# Display.net
KiCad netlist of a schematic drawn in EAGLE
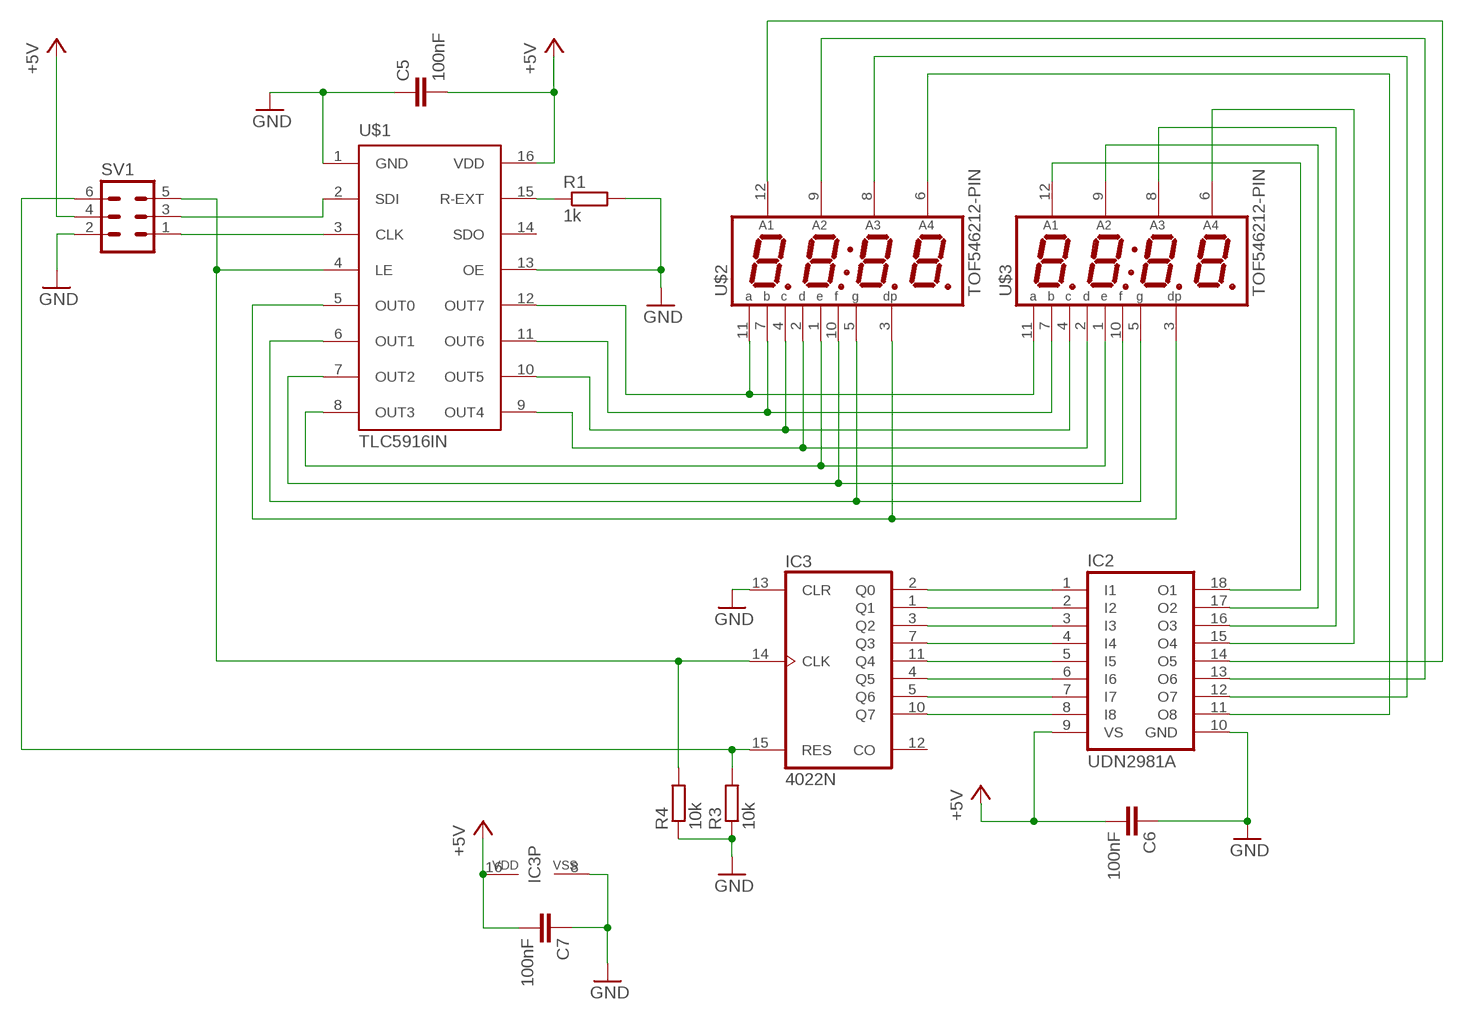
[diagram p0: schematic, sheet 1]

(export (version "E")
  (design (tool "Eeschema 10.0.6"))
  (components
    (comp (ref "C5")
      (value "100nF")
      (footprint "eagle-import:C025-024X044")
      (libsource (lib "eagle-import") (part "C-EU025-024X044"))
    )
    (comp (ref "C6")
      (value "100nF")
      (footprint "eagle-import:C025-024X044")
      (libsource (lib "eagle-import") (part "C-EU025-024X044"))
    )
    (comp (ref "C7")
      (value "100nF")
      (footprint "eagle-import:C025-024X044")
      (libsource (lib "eagle-import") (part "C-EU025-024X044"))
    )
    (comp (ref "IC2")
      (value "UDN2981A")
      (footprint "eagle-import:DIL18")
      (libsource (lib "eagle-import") (part "UDN298A1"))
    )
    (comp (ref "IC3")
      (value "4022N")
      (footprint "eagle-import:DIL16")
      (libsource (lib "eagle-import") (part "4022N"))
    )
    (comp (ref "R1")
      (value "1k")
      (footprint "eagle-import:0204_7")
      (libsource (lib "eagle-import") (part "R-EU_0204/7"))
    )
    (comp (ref "R3")
      (value "10k")
      (footprint "eagle-import:0204V")
      (libsource (lib "eagle-import") (part "R-EU_0204/2V"))
    )
    (comp (ref "R4")
      (value "10k")
      (footprint "eagle-import:0204V")
      (libsource (lib "eagle-import") (part "R-EU_0204/2V"))
    )
    (comp (ref "SV1")
      (value "ML6L")
      (footprint "eagle-import:ML6L")
      (libsource (lib "eagle-import") (part "ML6L"))
    )
    (comp (ref "U$1")
      (value "TLC5916IN")
      (footprint "eagle-import:DIL16")
      (libsource (lib "eagle-import") (part "TLC5916IN"))
    )
    (comp (ref "U$2")
      (value "TOF546212-PIN")
      (footprint "eagle-import:TOF5462_")
      (libsource (lib "eagle-import") (part "TOF546212-PIN"))
    )
    (comp (ref "U$3")
      (value "TOF546212-PIN")
      (footprint "eagle-import:TOF5462_")
      (libsource (lib "eagle-import") (part "TOF546212-PIN"))
    )
  )
  (nets
    (net (code "1") (name "+5V") (class "Default")
      (node (ref "C5") (pin "2") (pinfunction "2_2") (pintype "passive"))
      (node (ref "C6") (pin "2") (pinfunction "2_2") (pintype "passive"))
      (node (ref "C7") (pin "2") (pinfunction "2_2") (pintype "passive"))
      (node (ref "IC2") (pin "9") (pinfunction "VS_9") (pintype "passive"))
      (node (ref "IC3") (pin "16") (pinfunction "VDD_16") (pintype "power_in"))
      (node (ref "SV1") (pin "4") (pinfunction "4_4") (pintype "passive"))
      (node (ref "U$1") (pin "16") (pinfunction "VDD_16") (pintype "power_in"))
    )
    (net (code "2") (name "GND") (class "Default")
      (node (ref "C5") (pin "1") (pinfunction "1_1") (pintype "passive"))
      (node (ref "C6") (pin "1") (pinfunction "1_1") (pintype "passive"))
      (node (ref "C7") (pin "1") (pinfunction "1_1") (pintype "passive"))
      (node (ref "IC2") (pin "10") (pinfunction "GND_10") (pintype "power_in"))
      (node (ref "IC3") (pin "13") (pinfunction "CLR_13") (pintype "input"))
      (node (ref "IC3") (pin "8") (pinfunction "VSS_8") (pintype "power_in"))
      (node (ref "R1") (pin "2") (pinfunction "2_2") (pintype "passive"))
      (node (ref "R3") (pin "1") (pinfunction "1_1") (pintype "passive"))
      (node (ref "R4") (pin "1") (pinfunction "1_1") (pintype "passive"))
      (node (ref "SV1") (pin "2") (pinfunction "2_2") (pintype "passive"))
      (node (ref "U$1") (pin "1") (pinfunction "GND_1") (pintype "power_in"))
      (node (ref "U$1") (pin "13") (pinfunction "OE_13") (pintype "input"))
    )
    (net (code "3") (name "Net-(IC2-I1)") (class "Default")
      (node (ref "IC2") (pin "1") (pinfunction "I1_1") (pintype "input"))
      (node (ref "IC3") (pin "2") (pinfunction "Q0_2") (pintype "output"))
    )
    (net (code "4") (name "Net-(IC2-I2)") (class "Default")
      (node (ref "IC2") (pin "2") (pinfunction "I2_2") (pintype "input"))
      (node (ref "IC3") (pin "1") (pinfunction "Q1_1") (pintype "output"))
    )
    (net (code "5") (name "Net-(IC2-I3)") (class "Default")
      (node (ref "IC2") (pin "3") (pinfunction "I3_3") (pintype "input"))
      (node (ref "IC3") (pin "3") (pinfunction "Q2_3") (pintype "output"))
    )
    (net (code "6") (name "Net-(IC2-I4)") (class "Default")
      (node (ref "IC2") (pin "4") (pinfunction "I4_4") (pintype "input"))
      (node (ref "IC3") (pin "7") (pinfunction "Q3_7") (pintype "output"))
    )
    (net (code "7") (name "Net-(IC2-I5)") (class "Default")
      (node (ref "IC2") (pin "5") (pinfunction "I5_5") (pintype "input"))
      (node (ref "IC3") (pin "11") (pinfunction "Q4_11") (pintype "output"))
    )
    (net (code "8") (name "Net-(IC2-I6)") (class "Default")
      (node (ref "IC2") (pin "6") (pinfunction "I6_6") (pintype "input"))
      (node (ref "IC3") (pin "4") (pinfunction "Q5_4") (pintype "output"))
    )
    (net (code "9") (name "Net-(IC2-I7)") (class "Default")
      (node (ref "IC2") (pin "7") (pinfunction "I7_7") (pintype "input"))
      (node (ref "IC3") (pin "5") (pinfunction "Q6_5") (pintype "output"))
    )
    (net (code "10") (name "Net-(IC2-I8)") (class "Default")
      (node (ref "IC2") (pin "8") (pinfunction "I8_8") (pintype "input"))
      (node (ref "IC3") (pin "10") (pinfunction "Q7_10") (pintype "output"))
    )
    (net (code "11") (name "Net-(IC2-O1)") (class "Default")
      (node (ref "IC2") (pin "18") (pinfunction "O1_18") (pintype "open_collector"))
      (node (ref "U$3") (pin "12") (pinfunction "A1_12") (pintype "passive"))
    )
    (net (code "12") (name "Net-(IC2-O2)") (class "Default")
      (node (ref "IC2") (pin "17") (pinfunction "O2_17") (pintype "open_collector"))
      (node (ref "U$3") (pin "9") (pinfunction "A2_9") (pintype "passive"))
    )
    (net (code "13") (name "Net-(IC2-O3)") (class "Default")
      (node (ref "IC2") (pin "16") (pinfunction "O3_16") (pintype "open_collector"))
      (node (ref "U$3") (pin "8") (pinfunction "A3_8") (pintype "passive"))
    )
    (net (code "14") (name "Net-(IC2-O4)") (class "Default")
      (node (ref "IC2") (pin "15") (pinfunction "O4_15") (pintype "open_collector"))
      (node (ref "U$3") (pin "6") (pinfunction "A4_6") (pintype "passive"))
    )
    (net (code "15") (name "Net-(IC2-O5)") (class "Default")
      (node (ref "IC2") (pin "14") (pinfunction "O5_14") (pintype "open_collector"))
      (node (ref "U$2") (pin "12") (pinfunction "A1_12") (pintype "passive"))
    )
    (net (code "16") (name "Net-(IC2-O6)") (class "Default")
      (node (ref "IC2") (pin "13") (pinfunction "O6_13") (pintype "open_collector"))
      (node (ref "U$2") (pin "9") (pinfunction "A2_9") (pintype "passive"))
    )
    (net (code "17") (name "Net-(IC2-O7)") (class "Default")
      (node (ref "IC2") (pin "12") (pinfunction "O7_12") (pintype "open_collector"))
      (node (ref "U$2") (pin "8") (pinfunction "A3_8") (pintype "passive"))
    )
    (net (code "18") (name "Net-(IC2-O8)") (class "Default")
      (node (ref "IC2") (pin "11") (pinfunction "O8_11") (pintype "open_collector"))
      (node (ref "U$2") (pin "6") (pinfunction "A4_6") (pintype "passive"))
    )
    (net (code "19") (name "Net-(IC3A-CLK)") (class "Default")
      (node (ref "IC3") (pin "14") (pinfunction "CLK_14") (pintype "input"))
      (node (ref "R4") (pin "2") (pinfunction "2_2") (pintype "passive"))
      (node (ref "SV1") (pin "5") (pinfunction "5_5") (pintype "passive"))
      (node (ref "U$1") (pin "4") (pinfunction "LE_4") (pintype "input"))
    )
    (net (code "20") (name "Net-(IC3A-RES)") (class "Default")
      (node (ref "IC3") (pin "15") (pinfunction "RES_15") (pintype "input"))
      (node (ref "R3") (pin "2") (pinfunction "2_2") (pintype "passive"))
      (node (ref "SV1") (pin "6") (pinfunction "6_6") (pintype "passive"))
    )
    (net (code "21") (name "Net-(U$1-CLK)") (class "Default")
      (node (ref "SV1") (pin "1") (pinfunction "1_1") (pintype "passive"))
      (node (ref "U$1") (pin "3") (pinfunction "CLK_3") (pintype "input"))
    )
    (net (code "22") (name "Net-(U$1-OUT0)") (class "Default")
      (node (ref "U$1") (pin "5") (pinfunction "OUT0_5") (pintype "output"))
      (node (ref "U$2") (pin "3") (pinfunction "DP_3") (pintype "passive"))
      (node (ref "U$3") (pin "3") (pinfunction "DP_3") (pintype "passive"))
    )
    (net (code "23") (name "Net-(U$1-OUT1)") (class "Default")
      (node (ref "U$1") (pin "6") (pinfunction "OUT1_6") (pintype "output"))
      (node (ref "U$2") (pin "5") (pinfunction "G_5") (pintype "passive"))
      (node (ref "U$3") (pin "5") (pinfunction "G_5") (pintype "passive"))
    )
    (net (code "24") (name "Net-(U$1-OUT2)") (class "Default")
      (node (ref "U$1") (pin "7") (pinfunction "OUT2_7") (pintype "output"))
      (node (ref "U$2") (pin "10") (pinfunction "F_10") (pintype "passive"))
      (node (ref "U$3") (pin "10") (pinfunction "F_10") (pintype "passive"))
    )
    (net (code "25") (name "Net-(U$1-OUT3)") (class "Default")
      (node (ref "U$1") (pin "8") (pinfunction "OUT3_8") (pintype "output"))
      (node (ref "U$2") (pin "1") (pinfunction "E_1") (pintype "passive"))
      (node (ref "U$3") (pin "1") (pinfunction "E_1") (pintype "passive"))
    )
    (net (code "26") (name "Net-(U$1-OUT4)") (class "Default")
      (node (ref "U$1") (pin "9") (pinfunction "OUT4_9") (pintype "output"))
      (node (ref "U$2") (pin "2") (pinfunction "D_2") (pintype "passive"))
      (node (ref "U$3") (pin "2") (pinfunction "D_2") (pintype "passive"))
    )
    (net (code "27") (name "Net-(U$1-OUT5)") (class "Default")
      (node (ref "U$1") (pin "10") (pinfunction "OUT5_10") (pintype "output"))
      (node (ref "U$2") (pin "4") (pinfunction "C_4") (pintype "passive"))
      (node (ref "U$3") (pin "4") (pinfunction "C_4") (pintype "passive"))
    )
    (net (code "28") (name "Net-(U$1-OUT6)") (class "Default")
      (node (ref "U$1") (pin "11") (pinfunction "OUT6_11") (pintype "output"))
      (node (ref "U$2") (pin "7") (pinfunction "B_7") (pintype "passive"))
      (node (ref "U$3") (pin "7") (pinfunction "B_7") (pintype "passive"))
    )
    (net (code "29") (name "Net-(U$1-OUT7)") (class "Default")
      (node (ref "U$1") (pin "12") (pinfunction "OUT7_12") (pintype "output"))
      (node (ref "U$2") (pin "11") (pinfunction "A_11") (pintype "passive"))
      (node (ref "U$3") (pin "11") (pinfunction "A_11") (pintype "passive"))
    )
    (net (code "30") (name "Net-(U$1-R-EXT)") (class "Default")
      (node (ref "R1") (pin "1") (pinfunction "1_1") (pintype "passive"))
      (node (ref "U$1") (pin "15") (pinfunction "R-EXT_15") (pintype "input"))
    )
    (net (code "31") (name "Net-(U$1-SDI)") (class "Default")
      (node (ref "SV1") (pin "3") (pinfunction "3_3") (pintype "passive"))
      (node (ref "U$1") (pin "2") (pinfunction "SDI_2") (pintype "input"))
    )
    (net (code "32") (name "unconnected-(IC3A-CO-Pad12)") (class "Default")
      (node (ref "IC3") (pin "12") (pinfunction "CO_12") (pintype "output"))
    )
    (net (code "33") (name "unconnected-(U$1-SDO-Pad14)") (class "Default")
      (node (ref "U$1") (pin "14") (pinfunction "SDO_14") (pintype "output"))
    )
  )
)
